# Sheet_2.net
KiCad netlist of a schematic drawn in Altium Designer
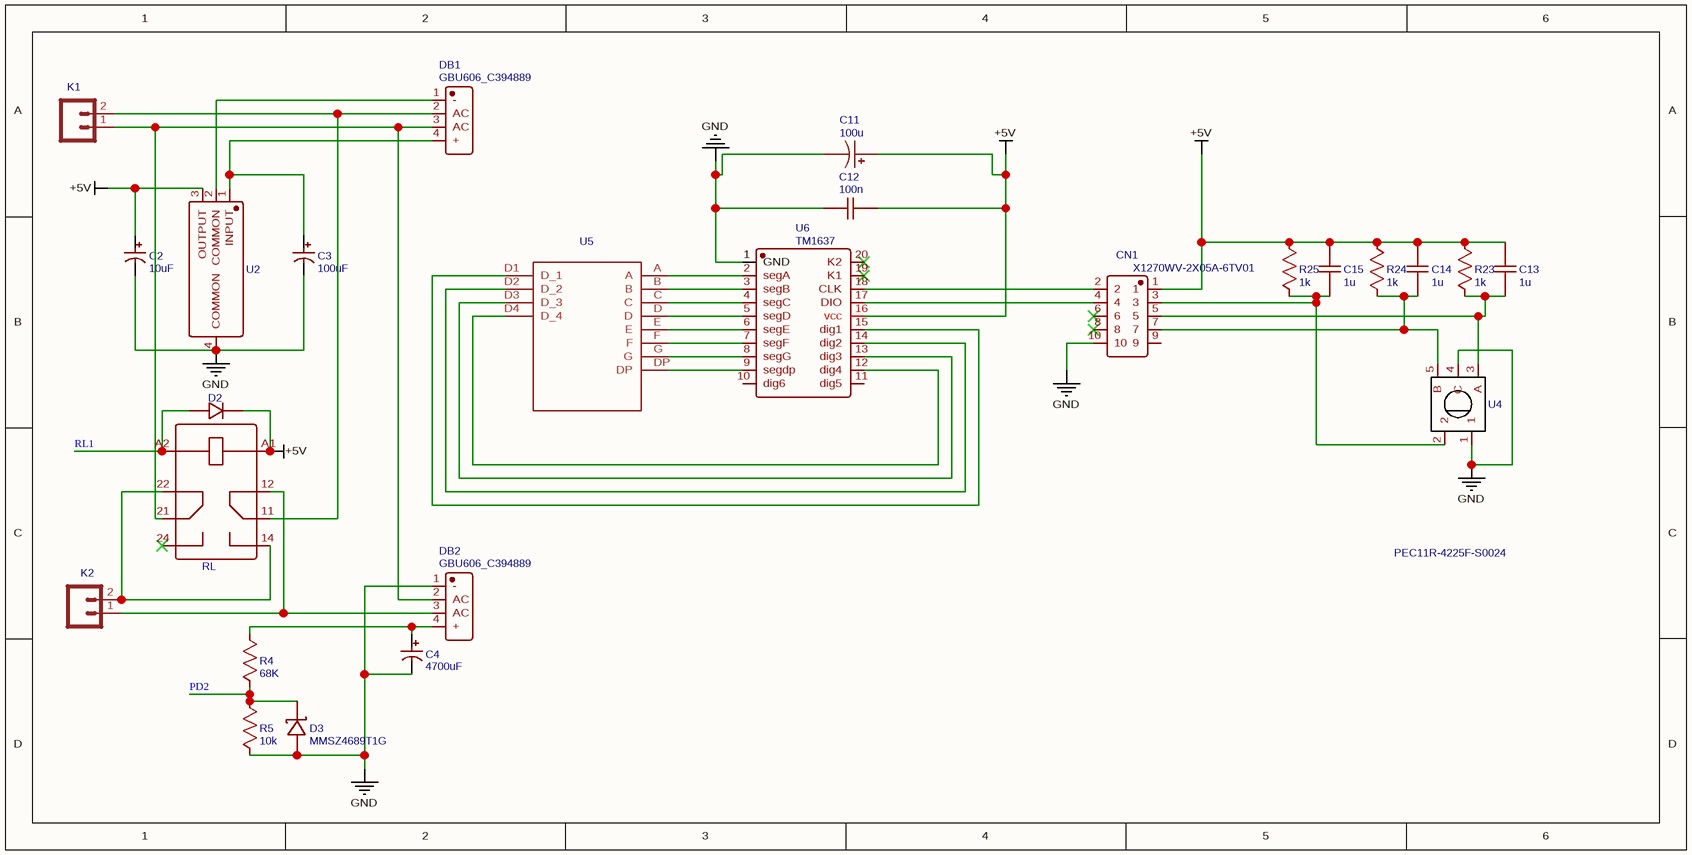
[diagram p0: Sheet_2.schdoc]

(export (version "E")
  (design (tool "Eeschema 10.0.6"))
  (components
    (comp (ref "C2")
      (value "10uF")
      (fields
        (field (name "BOM_MANUFACTURER PART") "25MS710MEFC4X7")
        (field (name "BOM_SUPPLIER PART") "C88739")
      )
      (libsource (lib "altium-import") (part "root_3_10uF_"))
    )
    (comp (ref "C3")
      (value "100uF")
      (fields
        (field (name "BOM_MANUFACTURER PART") "25YXJ100M5X11")
        (field (name "BOM_SUPPLIER PART") "C108360")
      )
      (libsource (lib "altium-import") (part "root_3_100uF_"))
    )
    (comp (ref "C4")
      (value "4700uF")
      (fields
        (field (name "BOM_MANUFACTURER PART") "4700uF 50V 22*35")
        (field (name "BOM_SUPPLIER PART") "C45662")
      )
      (libsource (lib "altium-import") (part "root_3_4700uF_"))
    )
    (comp (ref "C11")
      (value "100u")
      (fields (field (name "CONTRIBUTOR") "LCEDA_Lib"))
      (libsource (lib "altium-import") (part "root_2_100u_"))
    )
    (comp (ref "C12")
      (value "100n")
      (fields (field (name "CONTRIBUTOR") "LCEDA_Lib"))
      (libsource (lib "altium-import") (part "root_0_100n_"))
    )
    (comp (ref "C13")
      (value "1u")
      (fields (field (name "CONTRIBUTOR") "LCEDA_Lib"))
      (libsource (lib "altium-import") (part "root_1_1u_"))
    )
    (comp (ref "C14")
      (value "1u")
      (fields (field (name "CONTRIBUTOR") "LCEDA_Lib"))
      (libsource (lib "altium-import") (part "root_1_1u_"))
    )
    (comp (ref "C15")
      (value "1u")
      (fields (field (name "CONTRIBUTOR") "LCEDA_Lib"))
      (libsource (lib "altium-import") (part "root_1_1u_"))
    )
    (comp (ref "CN1")
      (value "X1270WV-2X05A-6TV01")
      (fields
        (field (name "BOM_SUPPLIER PART") "C2962228")
        (field (name "BOM_MANUFACTURER PART") "X1270WV-2x05A-6TV01")
        (field (name "CONTRIBUTOR") "LCSC")
      )
      (libsource (lib "altium-import") (part "root_0_X1270WV-2X05A-6TV01_"))
    )
    (comp (ref "D2")
      (value "1N4007W")
      (fields (field (name "BOM_SUPPLIER PART") "C328592") (field (name "CONTRIBUTOR") "LCEDA_Lib"))
      (libsource (lib "altium-import") (part "root_0_1N4007W_"))
    )
    (comp (ref "D3")
      (value "MMSZ4689T1G")
      (fields (field (name "BOM_SUPPLIER PART") "C236187") (field (name "CONTRIBUTOR") "LCSC"))
      (libsource (lib "altium-import") (part "root_3_MMSZ4689T1G_"))
    )
    (comp (ref "DB1")
      (value "GBU606_C394889")
      (fields
        (field (name "BOM_SUPPLIER PART") "C394889")
        (field (name "BOM_MANUFACTURER PART") "GBU606")
        (field (name "CONTRIBUTOR") "LCSC")
      )
      (libsource (lib "altium-import") (part "root_0_GBU606_C394889_"))
    )
    (comp (ref "DB2")
      (value "GBU606_C394889")
      (fields
        (field (name "BOM_SUPPLIER PART") "C394889")
        (field (name "BOM_MANUFACTURER PART") "GBU606")
        (field (name "CONTRIBUTOR") "LCSC")
      )
      (libsource (lib "altium-import") (part "root_0_GBU606_C394889_"))
    )
    (comp (ref "K1")
      (value "M025MM")
      (description "Standard 2-pin 0.1 header. Use with")
      (fields (field (name "CONTRIBUTOR") "SparkFun"))
      (libsource (lib "altium-import") (part "root_0_M025MM_"))
    )
    (comp (ref "K2")
      (value "M025MM")
      (description "Standard 2-pin 0.1 header. Use with")
      (fields (field (name "CONTRIBUTOR") "SparkFun"))
      (libsource (lib "altium-import") (part "root_0_M025MM_"))
    )
    (comp (ref "R4")
      (value "68K")
      (fields (field (name "CONTRIBUTOR") "LCEDA_Lib"))
      (libsource (lib "altium-import") (part "root_1_68K_"))
    )
    (comp (ref "R5")
      (value "10k")
      (fields (field (name "CONTRIBUTOR") "LCEDA_Lib"))
      (libsource (lib "altium-import") (part "root_1_10k_"))
    )
    (comp (ref "R23")
      (value "1k")
      (fields (field (name "CONTRIBUTOR") "LCEDA_Lib"))
      (libsource (lib "altium-import") (part "root_1_1k_"))
    )
    (comp (ref "R24")
      (value "1k")
      (fields (field (name "CONTRIBUTOR") "LCEDA_Lib"))
      (libsource (lib "altium-import") (part "root_1_1k_"))
    )
    (comp (ref "R25")
      (value "1k")
      (fields (field (name "CONTRIBUTOR") "LCEDA_Lib"))
      (libsource (lib "altium-import") (part "root_1_1k_"))
    )
    (comp (ref "RL")
      (value "RT424005F")
      (fields (field (name "BOM_SUPPLIER PART") "C1563228") (field (name "CONTRIBUTOR") "LCSC"))
      (libsource (lib "altium-import") (part "root_3_RT424005F_"))
    )
    (comp (ref "U2")
      (value "TL780-05CKTTR")
      (fields (field (name "BOM_SUPPLIER PART") "C485531") (field (name "CONTRIBUTOR") "LCSC"))
      (libsource (lib "altium-import") (part "root_3_TL780-05CKTTR_"))
    )
    (comp (ref "U4")
      (value "PEC11R-4225F-S0024")
      (fields (field (name "CONTRIBUTOR") "Morgan Proffitt"))
      (libsource (lib "altium-import") (part "root_2_PEC11R-4225F-S0024_"))
    )
    (comp (ref "U5")
      (value "4_DIGIT_7-SEGMENT_DISPLAYTHROUGH_HOLE")
      (libsource (lib "altium-import") (part "root_0_4_DIGIT_7-SEGMENT_DISPLAYTHROUGH_HOLE_"))
    )
    (comp (ref "U6")
      (value "TM1637")
      (fields (field (name "CONTRIBUTOR") "DanPo"))
      (libsource (lib "altium-import") (part "root_0_TM1637_"))
    )
  )
  (nets
    (net (code "1") (name "+5V") (class "Default")
      (node (ref "C11") (pin "1") (pinfunction "1_1") (pintype "passive"))
      (node (ref "C12") (pin "2") (pinfunction "2_2") (pintype "passive"))
      (node (ref "C13") (pin "2") (pinfunction "2_2") (pintype "passive"))
      (node (ref "C14") (pin "2") (pinfunction "2_2") (pintype "passive"))
      (node (ref "C15") (pin "2") (pinfunction "2_2") (pintype "passive"))
      (node (ref "C2") (pin "1") (pinfunction "1_1") (pintype "passive"))
      (node (ref "CN1") (pin "1") (pinfunction "1_1") (pintype "passive"))
      (node (ref "D2") (pin "1") (pinfunction "1_1") (pintype "passive"))
      (node (ref "R23") (pin "2") (pinfunction "2_2") (pintype "passive"))
      (node (ref "R24") (pin "2") (pinfunction "2_2") (pintype "passive"))
      (node (ref "R25") (pin "2") (pinfunction "2_2") (pintype "passive"))
      (node (ref "RL") (pin "A1") (pinfunction "A1_A1") (pintype "passive"))
      (node (ref "U2") (pin "3") (pinfunction "OUTPUT_3") (pintype "passive"))
      (node (ref "U6") (pin "16") (pinfunction "vcc_16") (pintype "passive"))
    )
    (net (code "2") (name "/PD2") (class "Default")
      (node (ref "D3") (pin "1") (pinfunction "K_1") (pintype "passive"))
      (node (ref "R4") (pin "1") (pinfunction "1_1") (pintype "passive"))
      (node (ref "R5") (pin "2") (pinfunction "2_2") (pintype "passive"))
    )
    (net (code "3") (name "/RL1") (class "Default")
      (node (ref "D2") (pin "2") (pinfunction "2_2") (pintype "passive"))
      (node (ref "RL") (pin "A2") (pinfunction "A2_A2") (pintype "passive"))
    )
    (net (code "4") (name "GND") (class "Default")
      (node (ref "C11") (pin "2") (pinfunction "2_2") (pintype "passive"))
      (node (ref "C12") (pin "1") (pinfunction "1_1") (pintype "passive"))
      (node (ref "C2") (pin "2") (pinfunction "2_2") (pintype "passive"))
      (node (ref "C3") (pin "2") (pinfunction "2_2") (pintype "passive"))
      (node (ref "C4") (pin "2") (pinfunction "2_2") (pintype "passive"))
      (node (ref "CN1") (pin "10") (pinfunction "10_10") (pintype "passive"))
      (node (ref "D3") (pin "2") (pinfunction "A_2") (pintype "passive"))
      (node (ref "DB2") (pin "1") (pinfunction "-_1") (pintype "passive"))
      (node (ref "R5") (pin "1") (pinfunction "1_1") (pintype "passive"))
      (node (ref "U2") (pin "4") (pinfunction "COMMON_4") (pintype "passive"))
      (node (ref "U4") (pin "1") (pinfunction "1_1") (pintype "passive"))
      (node (ref "U4") (pin "4") (pinfunction "C_4") (pintype "passive"))
      (node (ref "U6") (pin "1") (pinfunction "GND_1") (pintype "passive"))
    )
    (net (code "5") (name "Net-(C15-Pad1)") (class "Default")
      (node (ref "C15") (pin "1") (pinfunction "1_1") (pintype "passive"))
      (node (ref "CN1") (pin "3") (pinfunction "3_3") (pintype "passive"))
      (node (ref "R25") (pin "1") (pinfunction "1_1") (pintype "passive"))
      (node (ref "U4") (pin "2") (pinfunction "2_2") (pintype "passive"))
    )
    (net (code "6") (name "Net-(DB1-+)") (class "Default")
      (node (ref "C3") (pin "1") (pinfunction "1_1") (pintype "passive"))
      (node (ref "DB1") (pin "4") (pinfunction "+_4") (pintype "passive"))
      (node (ref "U2") (pin "1") (pinfunction "INPUT_1") (pintype "passive"))
    )
    (net (code "7") (name "Net-(DB1--)") (class "Default")
      (node (ref "DB1") (pin "1") (pinfunction "-_1") (pintype "passive"))
      (node (ref "U2") (pin "2") (pinfunction "COMMON_2") (pintype "passive"))
    )
    (net (code "8") (name "Net-(DB1-AC-Pad2)") (class "Default")
      (node (ref "DB1") (pin "2") (pinfunction "AC_2") (pintype "passive"))
      (node (ref "K1") (pin "2") (pinfunction "2_2") (pintype "passive"))
      (node (ref "RL") (pin "11") (pinfunction "11_11") (pintype "passive"))
    )
    (net (code "9") (name "Net-(DB1-AC-Pad3)") (class "Default")
      (node (ref "DB1") (pin "3") (pinfunction "AC_3") (pintype "passive"))
      (node (ref "DB2") (pin "2") (pinfunction "AC_2") (pintype "passive"))
      (node (ref "K1") (pin "1") (pinfunction "1_1") (pintype "passive"))
      (node (ref "RL") (pin "21") (pinfunction "21_21") (pintype "passive"))
    )
    (net (code "10") (name "Net-(DB2-+)") (class "Default")
      (node (ref "C4") (pin "1") (pinfunction "1_1") (pintype "passive"))
      (node (ref "DB2") (pin "4") (pinfunction "+_4") (pintype "passive"))
      (node (ref "R4") (pin "2") (pinfunction "2_2") (pintype "passive"))
    )
    (net (code "11") (name "Net-(DB2-AC-Pad3)") (class "Default")
      (node (ref "DB2") (pin "3") (pinfunction "AC_3") (pintype "passive"))
      (node (ref "K2") (pin "1") (pinfunction "1_1") (pintype "passive"))
      (node (ref "RL") (pin "12") (pinfunction "12_12") (pintype "passive"))
    )
    (net (code "12") (name "Net-(K2-Pad2)") (class "Default")
      (node (ref "K2") (pin "2") (pinfunction "2_2") (pintype "passive"))
      (node (ref "RL") (pin "14") (pinfunction "14_14") (pintype "passive"))
      (node (ref "RL") (pin "22") (pinfunction "22_22") (pintype "passive"))
    )
    (net (code "13") (name "Net-(U4-A)") (class "Default")
      (node (ref "C13") (pin "1") (pinfunction "1_1") (pintype "passive"))
      (node (ref "CN1") (pin "5") (pinfunction "5_5") (pintype "passive"))
      (node (ref "R23") (pin "1") (pinfunction "1_1") (pintype "passive"))
      (node (ref "U4") (pin "3") (pinfunction "A_3") (pintype "passive"))
    )
    (net (code "14") (name "Net-(U4-B)") (class "Default")
      (node (ref "C14") (pin "1") (pinfunction "1_1") (pintype "passive"))
      (node (ref "CN1") (pin "7") (pinfunction "7_7") (pintype "passive"))
      (node (ref "R24") (pin "1") (pinfunction "1_1") (pintype "passive"))
      (node (ref "U4") (pin "5") (pinfunction "B_5") (pintype "passive"))
    )
    (net (code "15") (name "Net-(U5-D_1)") (class "Default")
      (node (ref "U5") (pin "D1") (pinfunction "D_1_D1") (pintype "passive"))
      (node (ref "U6") (pin "15") (pinfunction "dig1_15") (pintype "passive"))
    )
    (net (code "16") (name "Net-(U5-D_2)") (class "Default")
      (node (ref "U5") (pin "D2") (pinfunction "D_2_D2") (pintype "passive"))
      (node (ref "U6") (pin "14") (pinfunction "dig2_14") (pintype "passive"))
    )
    (net (code "17") (name "Net-(U5-D_3)") (class "Default")
      (node (ref "U5") (pin "D3") (pinfunction "D_3_D3") (pintype "passive"))
      (node (ref "U6") (pin "13") (pinfunction "dig3_13") (pintype "passive"))
    )
    (net (code "18") (name "Net-(U5-D_4)") (class "Default")
      (node (ref "U5") (pin "D4") (pinfunction "D_4_D4") (pintype "passive"))
      (node (ref "U6") (pin "12") (pinfunction "dig4_12") (pintype "passive"))
    )
    (net (code "19") (name "Net-(U6-CLK)") (class "Default")
      (node (ref "CN1") (pin "2") (pinfunction "2_2") (pintype "passive"))
      (node (ref "U6") (pin "18") (pinfunction "CLK_18") (pintype "passive"))
    )
    (net (code "20") (name "Net-(U6-DIO)") (class "Default")
      (node (ref "CN1") (pin "4") (pinfunction "4_4") (pintype "passive"))
      (node (ref "U6") (pin "17") (pinfunction "DIO_17") (pintype "passive"))
    )
    (net (code "21") (name "Net-(U6-segA)") (class "Default")
      (node (ref "U5") (pin "A") (pinfunction "A_A") (pintype "passive"))
      (node (ref "U6") (pin "2") (pinfunction "segA_2") (pintype "passive"))
    )
    (net (code "22") (name "Net-(U6-segB)") (class "Default")
      (node (ref "U5") (pin "B") (pinfunction "B_B") (pintype "passive"))
      (node (ref "U6") (pin "3") (pinfunction "segB_3") (pintype "passive"))
    )
    (net (code "23") (name "Net-(U6-segC)") (class "Default")
      (node (ref "U5") (pin "C") (pinfunction "C_C") (pintype "passive"))
      (node (ref "U6") (pin "4") (pinfunction "segC_4") (pintype "passive"))
    )
    (net (code "24") (name "Net-(U6-segD)") (class "Default")
      (node (ref "U5") (pin "D") (pinfunction "D_D") (pintype "passive"))
      (node (ref "U6") (pin "5") (pinfunction "segD_5") (pintype "passive"))
    )
    (net (code "25") (name "Net-(U6-segE)") (class "Default")
      (node (ref "U5") (pin "E") (pinfunction "E_E") (pintype "passive"))
      (node (ref "U6") (pin "6") (pinfunction "segE_6") (pintype "passive"))
    )
    (net (code "26") (name "Net-(U6-segF)") (class "Default")
      (node (ref "U5") (pin "F") (pinfunction "F_F") (pintype "passive"))
      (node (ref "U6") (pin "7") (pinfunction "segF_7") (pintype "passive"))
    )
    (net (code "27") (name "Net-(U6-segG)") (class "Default")
      (node (ref "U5") (pin "G") (pinfunction "G_G") (pintype "passive"))
      (node (ref "U6") (pin "8") (pinfunction "segG_8") (pintype "passive"))
    )
    (net (code "28") (name "Net-(U6-segdp)") (class "Default")
      (node (ref "U5") (pin "DP") (pinfunction "DP_DP") (pintype "passive"))
      (node (ref "U6") (pin "9") (pinfunction "segdp_9") (pintype "passive"))
    )
    (net (code "29") (name "unconnected-(CN1-Pad6)") (class "Default")
      (node (ref "CN1") (pin "6") (pinfunction "6_6") (pintype "passive+no_connect"))
    )
    (net (code "30") (name "unconnected-(CN1-Pad8)") (class "Default")
      (node (ref "CN1") (pin "8") (pinfunction "8_8") (pintype "passive+no_connect"))
    )
    (net (code "31") (name "unconnected-(CN1-Pad9)") (class "Default")
      (node (ref "CN1") (pin "9") (pinfunction "9_9") (pintype "passive"))
    )
    (net (code "32") (name "unconnected-(RL-Pad24)") (class "Default")
      (node (ref "RL") (pin "24") (pinfunction "24_24") (pintype "passive+no_connect"))
    )
    (net (code "33") (name "unconnected-(U6-K1-Pad19)") (class "Default")
      (node (ref "U6") (pin "19") (pinfunction "K1_19") (pintype "passive+no_connect"))
    )
    (net (code "34") (name "unconnected-(U6-K2-Pad20)") (class "Default")
      (node (ref "U6") (pin "20") (pinfunction "K2_20") (pintype "passive+no_connect"))
    )
    (net (code "35") (name "unconnected-(U6-dig5-Pad11)") (class "Default")
      (node (ref "U6") (pin "11") (pinfunction "dig5_11") (pintype "passive"))
    )
    (net (code "36") (name "unconnected-(U6-dig6-Pad10)") (class "Default")
      (node (ref "U6") (pin "10") (pinfunction "dig6_10") (pintype "passive"))
    )
  )
)
